# 06_adc.net
KiCad netlist of a schematic drawn in Altium Designer
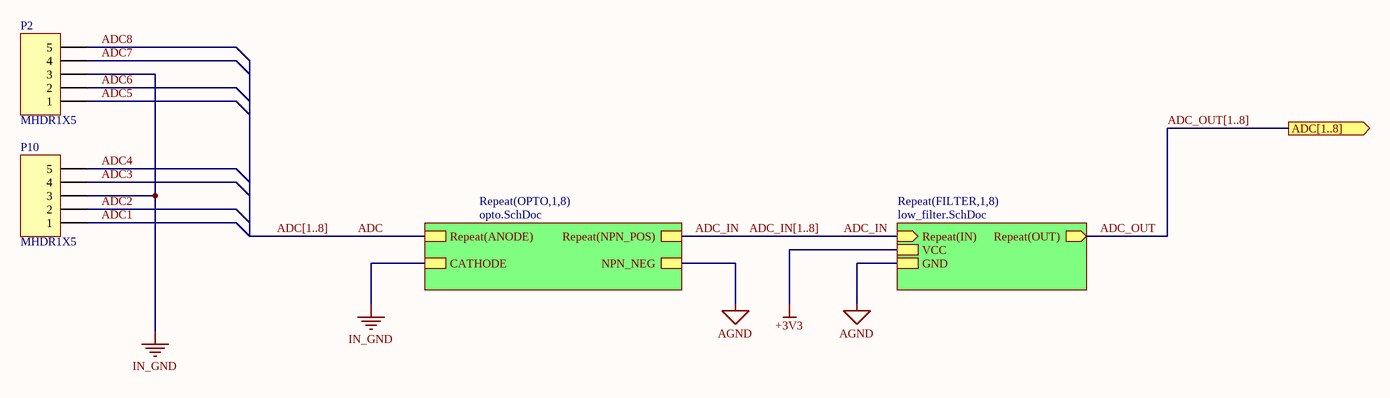
[diagram p0: 06_adc.SchDoc]

(export (version "E")
  (design (tool "Eeschema 10.0.6"))
  (components
    (comp (ref "P2")
      (value "MHDR1X5")
      (footprint "MHDR1X5")
      (description "Header, 5-Pin")
      (fields (field (name "PUBLISHER") "Altium Limited"))
      (libsource (lib "Miscellaneous Connectors") (part "MHDR1X5"))
    )
    (comp (ref "P10")
      (value "MHDR1X5")
      (footprint "MHDR1X5")
      (description "Header, 5-Pin")
      (fields (field (name "PUBLISHER") "Altium Limited"))
      (libsource (lib "Miscellaneous Connectors") (part "MHDR1X5"))
    )
  )
  (nets
    (net (code "19") (name "/ADC1") (class "Default")
      (node (ref "P10") (pin "1") (pinfunction "1_1") (pintype "passive"))
    )
    (net (code "20") (name "/ADC2") (class "Default")
      (node (ref "P10") (pin "2") (pinfunction "2_2") (pintype "passive"))
    )
    (net (code "21") (name "/ADC3") (class "Default")
      (node (ref "P10") (pin "4") (pinfunction "4_4") (pintype "passive"))
    )
    (net (code "22") (name "/ADC4") (class "Default")
      (node (ref "P10") (pin "5") (pinfunction "5_5") (pintype "passive"))
    )
    (net (code "23") (name "/ADC5") (class "Default")
      (node (ref "P2") (pin "1") (pinfunction "1_1") (pintype "passive"))
    )
    (net (code "24") (name "/ADC6") (class "Default")
      (node (ref "P2") (pin "2") (pinfunction "2_2") (pintype "passive"))
    )
    (net (code "25") (name "/ADC7") (class "Default")
      (node (ref "P2") (pin "4") (pinfunction "4_4") (pintype "passive"))
    )
    (net (code "26") (name "/ADC8") (class "Default")
      (node (ref "P2") (pin "5") (pinfunction "5_5") (pintype "passive"))
    )
    (net (code "31") (name "IN_GND") (class "Default")
      (node (ref "P10") (pin "3") (pinfunction "3_3") (pintype "passive"))
      (node (ref "P2") (pin "3") (pinfunction "3_3") (pintype "passive"))
    )
  )
)
